# CCDebugger-TagConnect.net
KiCad netlist of a schematic drawn in EAGLE
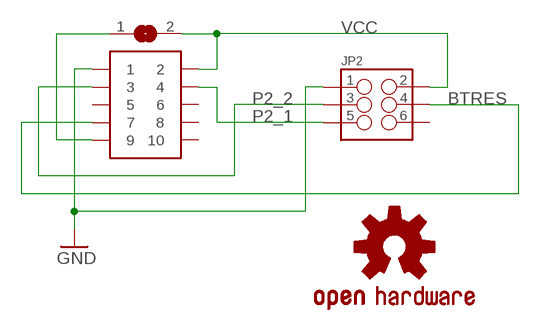
[diagram p0: schematic, sheet 1]

(export (version "E")
  (design (tool "Eeschema 10.0.6"))
  (components
    (comp (ref "JP2")
      (value "M03X2")
      (footprint "eagle-import:2X3-SHROUDED")
      (libsource (lib "eagle-import") (part "M03X2"))
    )
    (comp (ref "LOGO1")
      (value "OSHW-LOGOS")
      (footprint "eagle-import:OSHW-LOGO-S")
      (libsource (lib "eagle-import") (part "OSHW-LOGOS"))
    )
    (comp (ref "VCC") (value "SJ") (footprint "eagle-import:SJ") (libsource (lib "eagle-import") (part "SJ")))
    (comp (ref "X1")
      (value "CONN_5-2-FTSH-V")
      (footprint "eagle-import:FTSH-105-DV")
      (libsource (lib "eagle-import") (part "CONN_5-2-FTSH-V"))
    )
  )
  (nets
    (net (code "1") (name "/BTRES") (class "Default")
      (node (ref "JP2") (pin "4") (pinfunction "4_4") (pintype "bidirectional"))
      (node (ref "X1") (pin "7") (pinfunction "7_7") (pintype "bidirectional"))
    )
    (net (code "2") (name "/P2_1") (class "Default")
      (node (ref "JP2") (pin "5") (pinfunction "5_5") (pintype "bidirectional"))
      (node (ref "X1") (pin "4") (pinfunction "4_4") (pintype "bidirectional"))
    )
    (net (code "3") (name "/P2_2") (class "Default")
      (node (ref "JP2") (pin "3") (pinfunction "3_3") (pintype "bidirectional"))
      (node (ref "X1") (pin "3") (pinfunction "3_3") (pintype "bidirectional"))
    )
    (net (code "4") (name "/VCC") (class "Default")
      (node (ref "JP2") (pin "2") (pinfunction "2_2") (pintype "bidirectional"))
      (node (ref "VCC") (pin "2") (pinfunction "2_2") (pintype "passive"))
      (node (ref "X1") (pin "2") (pinfunction "2_2") (pintype "bidirectional"))
    )
    (net (code "5") (name "GND") (class "Default")
      (node (ref "JP2") (pin "1") (pinfunction "1_1") (pintype "bidirectional"))
      (node (ref "X1") (pin "1") (pinfunction "1_1") (pintype "bidirectional"))
    )
    (net (code "6") (name "Net-(VCC-Pad1)") (class "Default")
      (node (ref "VCC") (pin "1") (pinfunction "1_1") (pintype "passive"))
      (node (ref "X1") (pin "9") (pinfunction "9_9") (pintype "bidirectional"))
    )
    (net (code "7") (name "unconnected-(JP2-Pad6)") (class "Default")
      (node (ref "JP2") (pin "6") (pinfunction "6_6") (pintype "bidirectional"))
    )
    (net (code "8") (name "unconnected-(X1-Pad5)") (class "Default")
      (node (ref "X1") (pin "5") (pinfunction "5_5") (pintype "bidirectional"))
    )
    (net (code "9") (name "unconnected-(X1-Pad6)") (class "Default")
      (node (ref "X1") (pin "6") (pinfunction "6_6") (pintype "bidirectional"))
    )
    (net (code "10") (name "unconnected-(X1-Pad8)") (class "Default")
      (node (ref "X1") (pin "8") (pinfunction "8_8") (pintype "bidirectional"))
    )
    (net (code "11") (name "unconnected-(X1-Pad10)") (class "Default")
      (node (ref "X1") (pin "10") (pinfunction "10_10") (pintype "bidirectional"))
    )
  )
)
